# PlanktoscopeHat-v1_0-fab.net
KiCad netlist of a schematic drawn in EAGLE
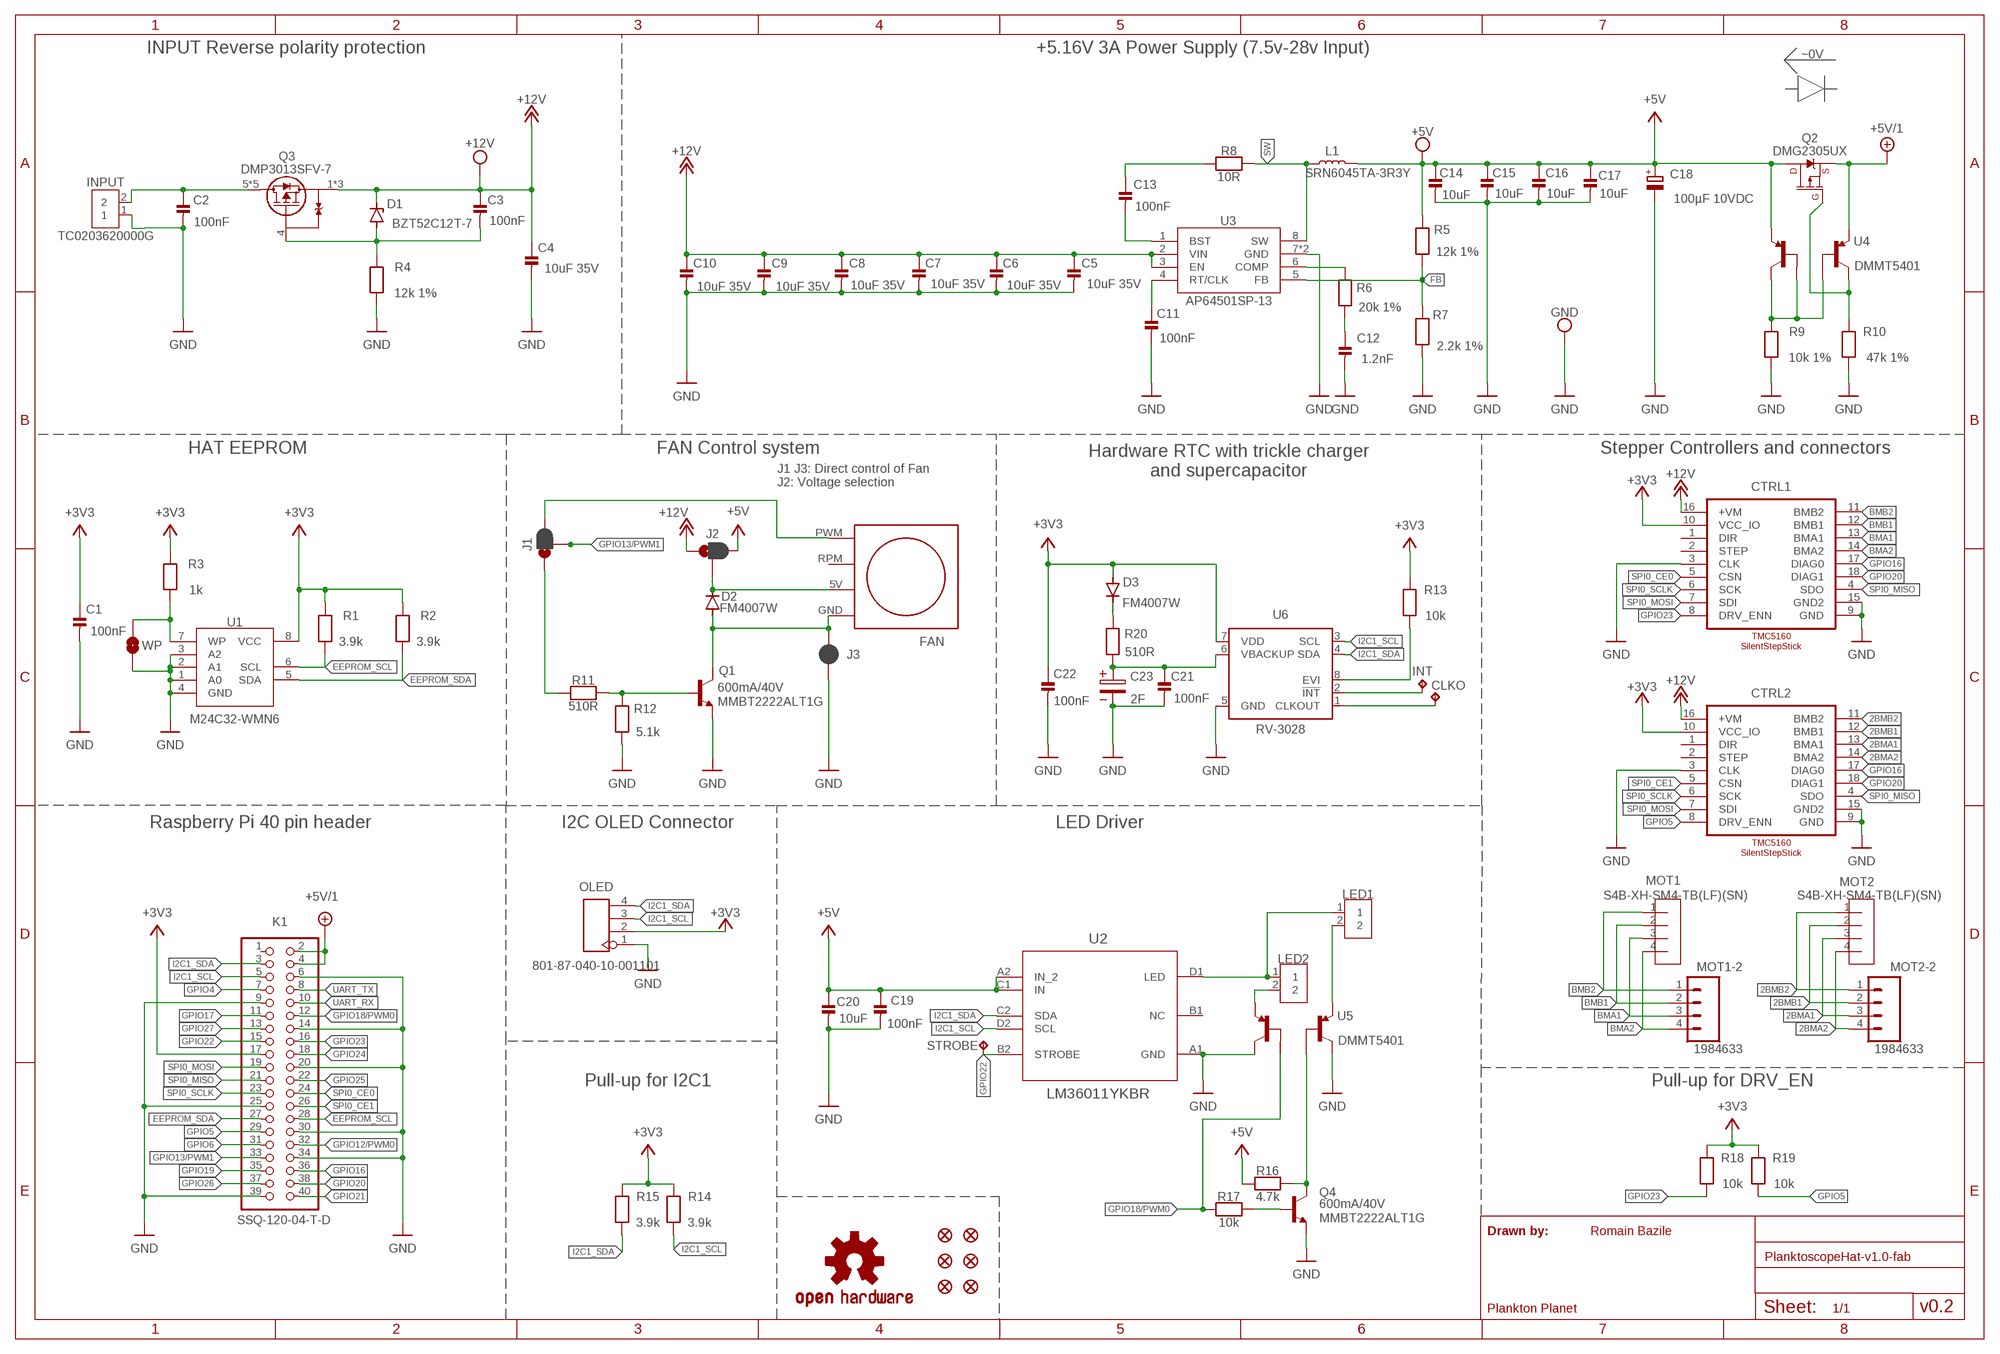
[diagram p0: schematic, sheet 1]

(export (version "E")
  (design (tool "Eeschema 10.0.6"))
  (components
    (comp (ref "+5V")
      (value "TESTPOINTPAD2MM")
      (footprint "eagle-import:TESTPOINT_PAD_2MM")
      (libsource (lib "eagle-import") (part "TESTPOINTPAD2MM"))
    )
    (comp (ref "+12V")
      (value "TESTPOINTPAD2MM")
      (footprint "eagle-import:TESTPOINT_PAD_2MM")
      (libsource (lib "eagle-import") (part "TESTPOINTPAD2MM"))
    )
    (comp (ref "C1")
      (value "100nF")
      (footprint "eagle-import:_0805MP")
      (libsource (lib "eagle-import") (part "CAP_CERAMIC_0805MP"))
    )
    (comp (ref "C2")
      (value "100nF")
      (footprint "eagle-import:_0805MP")
      (libsource (lib "eagle-import") (part "CAP_CERAMIC_0805MP"))
    )
    (comp (ref "C3")
      (value "100nF")
      (footprint "eagle-import:_0805MP")
      (libsource (lib "eagle-import") (part "CAP_CERAMIC_0805MP"))
    )
    (comp (ref "C4")
      (value "10uF 35V")
      (footprint "eagle-import:_0805MP")
      (libsource (lib "eagle-import") (part "CAP_CERAMIC_0805MP"))
    )
    (comp (ref "C5")
      (value "10uF 35V")
      (footprint "eagle-import:_0805MP")
      (libsource (lib "eagle-import") (part "CAP_CERAMIC_0805MP"))
    )
    (comp (ref "C6")
      (value "10uF 35V")
      (footprint "eagle-import:_0805MP")
      (libsource (lib "eagle-import") (part "CAP_CERAMIC_0805MP"))
    )
    (comp (ref "C7")
      (value "10uF 35V")
      (footprint "eagle-import:_0805MP")
      (libsource (lib "eagle-import") (part "CAP_CERAMIC_0805MP"))
    )
    (comp (ref "C8")
      (value "10uF 35V")
      (footprint "eagle-import:_0805MP")
      (libsource (lib "eagle-import") (part "CAP_CERAMIC_0805MP"))
    )
    (comp (ref "C9")
      (value "10uF 35V")
      (footprint "eagle-import:_0805MP")
      (libsource (lib "eagle-import") (part "CAP_CERAMIC_0805MP"))
    )
    (comp (ref "C10")
      (value "10uF 35V")
      (footprint "eagle-import:_0805MP")
      (libsource (lib "eagle-import") (part "CAP_CERAMIC_0805MP"))
    )
    (comp (ref "C11")
      (value "100nF")
      (footprint "eagle-import:_0805MP")
      (libsource (lib "eagle-import") (part "CAP_CERAMIC_0805MP"))
    )
    (comp (ref "C12")
      (value "1.2nF")
      (footprint "eagle-import:_0805MP")
      (libsource (lib "eagle-import") (part "CAP_CERAMIC_0805MP"))
    )
    (comp (ref "C13")
      (value "100nF")
      (footprint "eagle-import:_0805MP")
      (libsource (lib "eagle-import") (part "CAP_CERAMIC_0805MP"))
    )
    (comp (ref "C14")
      (value "10uF")
      (footprint "eagle-import:_0805MP")
      (libsource (lib "eagle-import") (part "CAP_CERAMIC_0805MP"))
    )
    (comp (ref "C15")
      (value "10uF")
      (footprint "eagle-import:_0805MP")
      (libsource (lib "eagle-import") (part "CAP_CERAMIC_0805MP"))
    )
    (comp (ref "C16")
      (value "10uF")
      (footprint "eagle-import:_0805MP")
      (libsource (lib "eagle-import") (part "CAP_CERAMIC_0805MP"))
    )
    (comp (ref "C17")
      (value "10uF")
      (footprint "eagle-import:_0805MP")
      (libsource (lib "eagle-import") (part "CAP_CERAMIC_0805MP"))
    )
    (comp (ref "C18")
      (value "100µF 10VDC")
      (footprint "eagle-import:CAPMP6032X280N")
      (fields (field (name "MPN") "TPSC107K010T0200"))
      (libsource (lib "eagle-import") (part "C-POLTANTALUM-2412(6032-METRIC)_"))
    )
    (comp (ref "C19")
      (value "100nF")
      (footprint "eagle-import:_0805MP")
      (libsource (lib "eagle-import") (part "CAP_CERAMIC_0805MP"))
    )
    (comp (ref "C20")
      (value "10uF")
      (footprint "eagle-import:_0805MP")
      (libsource (lib "eagle-import") (part "CAP_CERAMIC_0805MP"))
    )
    (comp (ref "C21")
      (value "100nF")
      (footprint "eagle-import:_0805MP")
      (libsource (lib "eagle-import") (part "CAP_CERAMIC_0805MP"))
    )
    (comp (ref "C22")
      (value "100nF")
      (footprint "eagle-import:_0805MP")
      (libsource (lib "eagle-import") (part "CAP_CERAMIC_0805MP"))
    )
    (comp (ref "C23")
      (value "2F")
      (footprint "eagle-import:8X3.5X0.9(DXAXB)")
      (fields (field (name "MPN") "SCCR12E105SRB"))
      (libsource (lib "eagle-import") (part "WCAP-PTHT_870135174001_8X8"))
    )
    (comp (ref "CLKO")
      (value "TPB1,27")
      (footprint "eagle-import:B1,27")
      (libsource (lib "eagle-import") (part "TPB1,27"))
    )
    (comp (ref "CTRL1")
      (value "TMC5160_SILENTSTEPSTICK")
      (footprint "eagle-import:TMC5160_STEPSTICK")
      (libsource (lib "eagle-import") (part "TMC5160_SILENTSTEPSTICK"))
    )
    (comp (ref "CTRL2")
      (value "TMC5160_SILENTSTEPSTICK")
      (footprint "eagle-import:TMC5160_STEPSTICK")
      (libsource (lib "eagle-import") (part "TMC5160_SILENTSTEPSTICK"))
    )
    (comp (ref "D1")
      (value "BZT52C12T-7")
      (footprint "eagle-import:SODFL1608X70")
      (libsource (lib "eagle-import") (part "ZENERSODFL(1608-METRIC)_"))
    )
    (comp (ref "D2")
      (value "FM4007W")
      (footprint "eagle-import:DO-214AC")
      (libsource (lib "eagle-import") (part "DIODE-DO-214AC"))
    )
    (comp (ref "D3")
      (value "FM4007W")
      (footprint "eagle-import:DO-214AC")
      (libsource (lib "eagle-import") (part "DIODE-DO-214AC"))
    )
    (comp (ref "FAN")
      (value "40MM_FAN")
      (footprint "eagle-import:40MM_FAN")
      (libsource (lib "eagle-import") (part "40MM_FAN"))
    )
    (comp (ref "FD1")
      (value "FIDUCIAL1X2")
      (footprint "eagle-import:FIDUCIAL-1X2")
      (libsource (lib "eagle-import") (part "FIDUCIAL1X2"))
    )
    (comp (ref "FD2")
      (value "FIDUCIAL1X2")
      (footprint "eagle-import:FIDUCIAL-1X2")
      (libsource (lib "eagle-import") (part "FIDUCIAL1X2"))
    )
    (comp (ref "FD3")
      (value "FIDUCIAL1X2")
      (footprint "eagle-import:FIDUCIAL-1X2")
      (libsource (lib "eagle-import") (part "FIDUCIAL1X2"))
    )
    (comp (ref "FD4")
      (value "FIDUCIAL1X2")
      (footprint "eagle-import:FIDUCIAL-1X2")
      (libsource (lib "eagle-import") (part "FIDUCIAL1X2"))
    )
    (comp (ref "FD5")
      (value "FIDUCIAL1X2")
      (footprint "eagle-import:FIDUCIAL-1X2")
      (libsource (lib "eagle-import") (part "FIDUCIAL1X2"))
    )
    (comp (ref "FD6")
      (value "FIDUCIAL1X2")
      (footprint "eagle-import:FIDUCIAL-1X2")
      (libsource (lib "eagle-import") (part "FIDUCIAL1X2"))
    )
    (comp (ref "GND")
      (value "TESTPOINTPAD2MM")
      (footprint "eagle-import:TESTPOINT_PAD_2MM")
      (libsource (lib "eagle-import") (part "TESTPOINTPAD2MM"))
    )
    (comp (ref "INPUT")
      (value "TC0203620000G")
      (footprint "eagle-import:TERMBLK_508-2N")
      (fields
        (field (name "MANUFACTURER") "TE Connectivity")
        (field (name "MPN") "282837-2")
        (field (name "MPN_1") "TC0203620000G")
      )
      (libsource (lib "eagle-import") (part "2828XX-2282837-2"))
    )
    (comp (ref "INT")
      (value "TPB1,27")
      (footprint "eagle-import:B1,27")
      (libsource (lib "eagle-import") (part "TPB1,27"))
    )
    (comp (ref "J1")
      (value "JUMPER-SMT_3_1-NC_PASTE_SILK")
      (footprint "eagle-import:SMT-JUMPER_3_1-NC_PASTE_SILK")
      (libsource (lib "eagle-import") (part "JUMPER-SMT_3_1-NC_PASTE_SILK"))
    )
    (comp (ref "J2")
      (value "JUMPER-SMT_3_1-NC_PASTE_SILK")
      (footprint "eagle-import:SMT-JUMPER_3_1-NC_PASTE_SILK")
      (libsource (lib "eagle-import") (part "JUMPER-SMT_3_1-NC_PASTE_SILK"))
    )
    (comp (ref "J3")
      (value "JUMPER-SMT_2_NC_PASTE_SILK")
      (footprint "eagle-import:SMT-JUMPER_2_NC_PASTE_SILK")
      (libsource (lib "eagle-import") (part "JUMPER-SMT_2_NC_PASTE_SILK"))
    )
    (comp (ref "K1")
      (value "SSQ-120-04-T-D")
      (footprint "eagle-import:2X20")
      (libsource (lib "eagle-import") (part "PINHD-2X20"))
    )
    (comp (ref "L1")
      (value "SRN6045TA-3R3Y")
      (footprint "eagle-import:SRN6045")
      (libsource (lib "eagle-import") (part "INDUCTOR-SRN6045-33UH"))
    )
    (comp (ref "LED1")
      (value "2828XX-2282834-2")
      (footprint "eagle-import:TERMBLK_254-2N")
      (libsource (lib "eagle-import") (part "2828XX-2282834-2"))
    )
    (comp (ref "LED2")
      (value "2828XX-2282834-2")
      (footprint "eagle-import:TERMBLK_254-2N")
      (libsource (lib "eagle-import") (part "2828XX-2282834-2"))
    )
    (comp (ref "LOGO1")
      (value "OSHW-LOGOL")
      (footprint "eagle-import:OSHW-LOGO-L")
      (libsource (lib "eagle-import") (part "OSHW-LOGOL"))
    )
    (comp (ref "MOT1")
      (value "S4B-XH-SM4-TB(LF)(SN)")
      (footprint "eagle-import:CONN_S4B-XH-SM4-TB_JST")
      (fields
        (field (name "MPN") "S4B-XH-SM4-TB(LF)(SN)")
        (field (name "COPYRIGHT") "Copyright (C) 2018 Accelerated Designs. All rights reserved")
      )
      (libsource (lib "eagle-import") (part "S4B-XH-SM4-TB(LF)(SN)"))
    )
    (comp (ref "MOT1-2")
      (value "1984633")
      (footprint "eagle-import:SCREWTERMINAL-3.5MM-4")
      (libsource (lib "eagle-import") (part "CONN_04SCREW"))
    )
    (comp (ref "MOT2")
      (value "S4B-XH-SM4-TB(LF)(SN)")
      (footprint "eagle-import:CONN_S4B-XH-SM4-TB_JST")
      (fields
        (field (name "MPN") "S4B-XH-SM4-TB(LF)(SN)")
        (field (name "COPYRIGHT") "Copyright (C) 2018 Accelerated Designs. All rights reserved")
      )
      (libsource (lib "eagle-import") (part "S4B-XH-SM4-TB(LF)(SN)"))
    )
    (comp (ref "MOT2-2")
      (value "1984633")
      (footprint "eagle-import:SCREWTERMINAL-3.5MM-4")
      (libsource (lib "eagle-import") (part "CONN_04SCREW"))
    )
    (comp (ref "OLED")
      (value "801-87-040-10-001101")
      (footprint "eagle-import:H4-2.54")
      (fields (field (name "MPN") "P125-1104A0BS116A1"))
      (libsource (lib "eagle-import") (part "DIP-BLACK-MALE-HEADER-VERT(4P-2.54)"))
    )
    (comp (ref "Q1")
      (value "600mA/40V")
      (footprint "eagle-import:SOT23-3")
      (fields (field (name "MPN") "MMBT2222ALT1G"))
      (libsource (lib "eagle-import") (part "TRANS_NPN-MMBT2222AL"))
    )
    (comp (ref "Q2")
      (value "DMG2305UX")
      (footprint "eagle-import:SOT23-3")
      (libsource (lib "eagle-import") (part "MOSFET_PCH-DMG2305UX-7"))
    )
    (comp (ref "Q3")
      (value "DMP3013SFV-7")
      (footprint "eagle-import:POWERDI3333-8_UX_DIO")
      (fields (field (name "COPYRIGHT") "Copyright (C) 2018 Accelerated Designs. All rights reserved"))
      (libsource (lib "eagle-import") (part "DMP3013SFV-7"))
    )
    (comp (ref "Q4")
      (value "600mA/40V")
      (footprint "eagle-import:SOT23-3")
      (fields (field (name "MPN") "MMBT2222ALT1G"))
      (libsource (lib "eagle-import") (part "TRANS_NPN-MMBT2222AL"))
    )
    (comp (ref "R1")
      (value "3.9k")
      (footprint "eagle-import:_0805MP")
      (libsource (lib "eagle-import") (part "RESISTOR_0805MP"))
    )
    (comp (ref "R2")
      (value "3.9k")
      (footprint "eagle-import:_0805MP")
      (libsource (lib "eagle-import") (part "RESISTOR_0805MP"))
    )
    (comp (ref "R3")
      (value "1k")
      (footprint "eagle-import:_0805MP")
      (libsource (lib "eagle-import") (part "RESISTOR_0805MP"))
    )
    (comp (ref "R4")
      (value "12k 1%")
      (footprint "eagle-import:_0805MP")
      (libsource (lib "eagle-import") (part "RESISTOR_0805MP"))
    )
    (comp (ref "R5")
      (value "12k 1%")
      (footprint "eagle-import:_0805MP")
      (libsource (lib "eagle-import") (part "RESISTOR_0805MP"))
    )
    (comp (ref "R6")
      (value "20k 1%")
      (footprint "eagle-import:_0805MP")
      (libsource (lib "eagle-import") (part "RESISTOR_0805MP"))
    )
    (comp (ref "R7")
      (value "2.2k 1%")
      (footprint "eagle-import:_0805MP")
      (libsource (lib "eagle-import") (part "RESISTOR_0805MP"))
    )
    (comp (ref "R8")
      (value "10R")
      (footprint "eagle-import:_0805MP")
      (libsource (lib "eagle-import") (part "RESISTOR_0805MP"))
    )
    (comp (ref "R9")
      (value "10k 1%")
      (footprint "eagle-import:_0805MP")
      (libsource (lib "eagle-import") (part "RESISTOR_0805MP"))
    )
    (comp (ref "R10")
      (value "47k 1%")
      (footprint "eagle-import:_0805MP")
      (libsource (lib "eagle-import") (part "RESISTOR_0805MP"))
    )
    (comp (ref "R11")
      (value "510R")
      (footprint "eagle-import:_0805MP")
      (libsource (lib "eagle-import") (part "RESISTOR_0805MP"))
    )
    (comp (ref "R12")
      (value "5.1k")
      (footprint "eagle-import:_0805MP")
      (libsource (lib "eagle-import") (part "RESISTOR_0805MP"))
    )
    (comp (ref "R13")
      (value "10k")
      (footprint "eagle-import:_0805MP")
      (libsource (lib "eagle-import") (part "RESISTOR_0805MP"))
    )
    (comp (ref "R14")
      (value "3.9k")
      (footprint "eagle-import:_0805MP")
      (libsource (lib "eagle-import") (part "RESISTOR_0805MP"))
    )
    (comp (ref "R15")
      (value "3.9k")
      (footprint "eagle-import:_0805MP")
      (libsource (lib "eagle-import") (part "RESISTOR_0805MP"))
    )
    (comp (ref "R16")
      (value "4.7k")
      (footprint "eagle-import:_0805MP")
      (libsource (lib "eagle-import") (part "RESISTOR_0805MP"))
    )
    (comp (ref "R17")
      (value "10k")
      (footprint "eagle-import:_0805MP")
      (libsource (lib "eagle-import") (part "RESISTOR_0805MP"))
    )
    (comp (ref "R18")
      (value "10k")
      (footprint "eagle-import:_0805MP")
      (libsource (lib "eagle-import") (part "RESISTOR_0805MP"))
    )
    (comp (ref "R19")
      (value "10k")
      (footprint "eagle-import:_0805MP")
      (libsource (lib "eagle-import") (part "RESISTOR_0805MP"))
    )
    (comp (ref "R20")
      (value "510R")
      (footprint "eagle-import:_0805MP")
      (libsource (lib "eagle-import") (part "RESISTOR_0805MP"))
    )
    (comp (ref "STROBE")
      (value "TPTP15R")
      (footprint "eagle-import:TP15R")
      (libsource (lib "eagle-import") (part "TPTP15R"))
    )
    (comp (ref "U1")
      (value "M24C32-WMN6")
      (footprint "eagle-import:SO-8_STM")
      (libsource (lib "eagle-import") (part "M24C32-WMN6"))
    )
    (comp (ref "U2")
      (value "LM36011YKBR")
      (footprint "eagle-import:YKB0008AGAG")
      (fields (field (name "MANUFACTURER") "Texas Instruments"))
      (libsource (lib "eagle-import") (part "LM36011YKBR"))
    )
    (comp (ref "U3")
      (value "AP64501SP-13")
      (footprint "eagle-import:SO-8EP_DIO")
      (fields
        (field (name "MANUFACTURER_PART_NUMBER") "AP64500SP-13")
        (field (name "COPYRIGHT") "Copyright (C) 2018 Accelerated Designs. All rights reserved")
      )
      (libsource (lib "eagle-import") (part "AP64500SP-13"))
    )
    (comp (ref "U4")
      (value "DMMT5401")
      (footprint "eagle-import:SOT26")
      (libsource (lib "eagle-import") (part "DDMT5401"))
    )
    (comp (ref "U5")
      (value "DMMT5401")
      (footprint "eagle-import:SOT26")
      (libsource (lib "eagle-import") (part "DDMT5401"))
    )
    (comp (ref "U6")
      (value "RV-3028")
      (footprint "eagle-import:RV-3028")
      (libsource (lib "eagle-import") (part "RV-3028"))
    )
    (comp (ref "WP")
      (value "JUMPER-SMT_2_NO_SILK")
      (footprint "eagle-import:SMT-JUMPER_2_NO_SILK")
      (libsource (lib "eagle-import") (part "JUMPER-SMT_2_NO_SILK"))
    )
  )
  (nets
    (net (code "1") (name "+3V3") (class "Default")
      (node (ref "C1") (pin "1") (pinfunction "1_1") (pintype "passive"))
      (node (ref "C22") (pin "1") (pinfunction "1_1") (pintype "passive"))
      (node (ref "CTRL1") (pin "10") (pinfunction "VCC_IO_10") (pintype "passive"))
      (node (ref "CTRL2") (pin "10") (pinfunction "VCC_IO_10") (pintype "passive"))
      (node (ref "D3") (pin "A") (pinfunction "A_A") (pintype "passive"))
      (node (ref "K1") (pin "17") (pinfunction "17_17") (pintype "passive"))
      (node (ref "OLED") (pin "2") (pinfunction "P$2_2") (pintype "bidirectional"))
      (node (ref "R1") (pin "2") (pinfunction "2_2") (pintype "passive"))
      (node (ref "R13") (pin "2") (pinfunction "2_2") (pintype "passive"))
      (node (ref "R14") (pin "2") (pinfunction "2_2") (pintype "passive"))
      (node (ref "R15") (pin "2") (pinfunction "2_2") (pintype "passive"))
      (node (ref "R18") (pin "2") (pinfunction "2_2") (pintype "passive"))
      (node (ref "R19") (pin "2") (pinfunction "2_2") (pintype "passive"))
      (node (ref "R2") (pin "2") (pinfunction "2_2") (pintype "passive"))
      (node (ref "R3") (pin "2") (pinfunction "2_2") (pintype "passive"))
      (node (ref "U1") (pin "8") (pinfunction "VCC_8") (pintype "power_in"))
      (node (ref "U6") (pin "7") (pinfunction "VDD_7") (pintype "bidirectional"))
    )
    (net (code "2") (name "+5V") (class "Default")
      (node (ref "+5V") (pin "P$1") (pinfunction "P$1_P$1") (pintype "bidirectional"))
      (node (ref "C14") (pin "1") (pinfunction "1_1") (pintype "passive"))
      (node (ref "C15") (pin "1") (pinfunction "1_1") (pintype "passive"))
      (node (ref "C16") (pin "1") (pinfunction "1_1") (pintype "passive"))
      (node (ref "C17") (pin "1") (pinfunction "1_1") (pintype "passive"))
      (node (ref "C18") (pin "1") (pinfunction "+_1") (pintype "passive"))
      (node (ref "C19") (pin "1") (pinfunction "1_1") (pintype "passive"))
      (node (ref "C20") (pin "1") (pinfunction "1_1") (pintype "passive"))
      (node (ref "J2") (pin "3") (pinfunction "3_3") (pintype "passive"))
      (node (ref "L1") (pin "2") (pinfunction "2_2") (pintype "passive"))
      (node (ref "Q2") (pin "3") (pinfunction "D_3") (pintype "bidirectional"))
      (node (ref "R16") (pin "2") (pinfunction "2_2") (pintype "passive"))
      (node (ref "R5") (pin "2") (pinfunction "2_2") (pintype "passive"))
      (node (ref "U2") (pin "A2") (pinfunction "IN_2_A2") (pintype "power_in"))
      (node (ref "U2") (pin "C1") (pinfunction "IN_C1") (pintype "power_in"))
      (node (ref "U4") (pin "D1") (pinfunction "6_D1") (pintype "passive"))
    )
    (net (code "3") (name "+5V{slash}1") (class "Default")
      (node (ref "K1") (pin "2") (pinfunction "2_2") (pintype "passive"))
      (node (ref "K1") (pin "4") (pinfunction "4_4") (pintype "passive"))
      (node (ref "Q2") (pin "2") (pinfunction "S_2") (pintype "bidirectional"))
      (node (ref "U4") (pin "S1") (pinfunction "5_S1") (pintype "passive"))
    )
    (net (code "4") (name "+12V") (class "Default")
      (node (ref "+12V") (pin "P$1") (pinfunction "P$1_P$1") (pintype "bidirectional"))
      (node (ref "C10") (pin "1") (pinfunction "1_1") (pintype "passive"))
      (node (ref "C3") (pin "1") (pinfunction "1_1") (pintype "passive"))
      (node (ref "C4") (pin "1") (pinfunction "1_1") (pintype "passive"))
      (node (ref "C5") (pin "1") (pinfunction "1_1") (pintype "passive"))
      (node (ref "C6") (pin "1") (pinfunction "1_1") (pintype "passive"))
      (node (ref "C7") (pin "1") (pinfunction "1_1") (pintype "passive"))
      (node (ref "C8") (pin "1") (pinfunction "1_1") (pintype "passive"))
      (node (ref "C9") (pin "1") (pinfunction "1_1") (pintype "passive"))
      (node (ref "CTRL1") (pin "16") (pinfunction "+VM_16") (pintype "passive"))
      (node (ref "CTRL2") (pin "16") (pinfunction "+VM_16") (pintype "passive"))
      (node (ref "D1") (pin "1") (pinfunction "C_1") (pintype "passive"))
      (node (ref "J2") (pin "1") (pinfunction "1_1") (pintype "passive"))
      (node (ref "Q3") (pin "1") (pinfunction "S_1") (pintype "passive"))
      (node (ref "Q3") (pin "2") (pinfunction "S_2") (pintype "passive"))
      (node (ref "Q3") (pin "3") (pinfunction "S_3") (pintype "passive"))
      (node (ref "U3") (pin "2") (pinfunction "VIN_2") (pintype "power_in"))
      (node (ref "U3") (pin "3") (pinfunction "EN_3") (pintype "input"))
    )
    (net (code "5") (name "2BMA1") (class "Default")
      (node (ref "CTRL2") (pin "13") (pinfunction "BMA1_13") (pintype "passive"))
      (node (ref "MOT2") (pin "3") (pinfunction "3_3") (pintype "passive"))
      (node (ref "MOT2-2") (pin "3") (pinfunction "3_3") (pintype "passive"))
    )
    (net (code "6") (name "2BMA2") (class "Default")
      (node (ref "CTRL2") (pin "14") (pinfunction "BMA2_14") (pintype "passive"))
      (node (ref "MOT2") (pin "4") (pinfunction "4_4") (pintype "passive"))
      (node (ref "MOT2-2") (pin "4") (pinfunction "4_4") (pintype "passive"))
    )
    (net (code "7") (name "2BMB1") (class "Default")
      (node (ref "CTRL2") (pin "12") (pinfunction "BMB1_12") (pintype "passive"))
      (node (ref "MOT2") (pin "2") (pinfunction "2_2") (pintype "passive"))
      (node (ref "MOT2-2") (pin "2") (pinfunction "2_2") (pintype "passive"))
    )
    (net (code "8") (name "2BMB2") (class "Default")
      (node (ref "CTRL2") (pin "11") (pinfunction "BMB2_11") (pintype "passive"))
      (node (ref "MOT2") (pin "1") (pinfunction "1_1") (pintype "passive"))
      (node (ref "MOT2-2") (pin "1") (pinfunction "1_1") (pintype "passive"))
    )
    (net (code "9") (name "BMA1") (class "Default")
      (node (ref "CTRL1") (pin "13") (pinfunction "BMA1_13") (pintype "passive"))
      (node (ref "MOT1") (pin "3") (pinfunction "3_3") (pintype "passive"))
      (node (ref "MOT1-2") (pin "3") (pinfunction "3_3") (pintype "passive"))
    )
    (net (code "10") (name "BMA2") (class "Default")
      (node (ref "CTRL1") (pin "14") (pinfunction "BMA2_14") (pintype "passive"))
      (node (ref "MOT1") (pin "4") (pinfunction "4_4") (pintype "passive"))
      (node (ref "MOT1-2") (pin "4") (pinfunction "4_4") (pintype "passive"))
    )
    (net (code "11") (name "BMB1") (class "Default")
      (node (ref "CTRL1") (pin "12") (pinfunction "BMB1_12") (pintype "passive"))
      (node (ref "MOT1") (pin "2") (pinfunction "2_2") (pintype "passive"))
      (node (ref "MOT1-2") (pin "2") (pinfunction "2_2") (pintype "passive"))
    )
    (net (code "12") (name "BMB2") (class "Default")
      (node (ref "CTRL1") (pin "11") (pinfunction "BMB2_11") (pintype "passive"))
      (node (ref "MOT1") (pin "1") (pinfunction "1_1") (pintype "passive"))
      (node (ref "MOT1-2") (pin "1") (pinfunction "1_1") (pintype "passive"))
    )
    (net (code "13") (name "EEPROM_SCL") (class "Default")
      (node (ref "K1") (pin "28") (pinfunction "28_28") (pintype "passive"))
      (node (ref "R1") (pin "1") (pinfunction "1_1") (pintype "passive"))
      (node (ref "U1") (pin "6") (pinfunction "SCL_6") (pintype "input"))
    )
    (net (code "14") (name "EEPROM_SDA") (class "Default")
      (node (ref "K1") (pin "27") (pinfunction "27_27") (pintype "passive"))
      (node (ref "R2") (pin "1") (pinfunction "1_1") (pintype "passive"))
      (node (ref "U1") (pin "5") (pinfunction "SDA_5") (pintype "bidirectional"))
    )
    (net (code "15") (name "FB") (class "Default")
      (node (ref "R5") (pin "1") (pinfunction "1_1") (pintype "passive"))
      (node (ref "R7") (pin "2") (pinfunction "2_2") (pintype "passive"))
      (node (ref "U3") (pin "5") (pinfunction "FB_5") (pintype "passive"))
    )
    (net (code "16") (name "GND") (class "Default")
      (node (ref "C1") (pin "2") (pinfunction "2_2") (pintype "passive"))
      (node (ref "C10") (pin "2") (pinfunction "2_2") (pintype "passive"))
      (node (ref "C11") (pin "2") (pinfunction "2_2") (pintype "passive"))
      (node (ref "C12") (pin "2") (pinfunction "2_2") (pintype "passive"))
      (node (ref "C14") (pin "2") (pinfunction "2_2") (pintype "passive"))
      (node (ref "C15") (pin "2") (pinfunction "2_2") (pintype "passive"))
      (node (ref "C16") (pin "2") (pinfunction "2_2") (pintype "passive"))
      (node (ref "C17") (pin "2") (pinfunction "2_2") (pintype "passive"))
      (node (ref "C18") (pin "2") (pinfunction "-_2") (pintype "passive"))
      (node (ref "C19") (pin "2") (pinfunction "2_2") (pintype "passive"))
      (node (ref "C2") (pin "2") (pinfunction "2_2") (pintype "passive"))
      (node (ref "C20") (pin "2") (pinfunction "2_2") (pintype "passive"))
      (node (ref "C21") (pin "2") (pinfunction "2_2") (pintype "passive"))
      (node (ref "C22") (pin "2") (pinfunction "2_2") (pintype "passive"))
      (node (ref "C23") (pin "2") (pinfunction "2_2") (pintype "passive"))
      (node (ref "C4") (pin "2") (pinfunction "2_2") (pintype "passive"))
      (node (ref "C5") (pin "2") (pinfunction "2_2") (pintype "passive"))
      (node (ref "C6") (pin "2") (pinfunction "2_2") (pintype "passive"))
      (node (ref "C7") (pin "2") (pinfunction "2_2") (pintype "passive"))
      (node (ref "C8") (pin "2") (pinfunction "2_2") (pintype "passive"))
      (node (ref "C9") (pin "2") (pinfunction "2_2") (pintype "passive"))
      (node (ref "CTRL1") (pin "15") (pinfunction "GND2_15") (pintype "passive"))
      (node (ref "CTRL1") (pin "3") (pinfunction "CLK_3") (pintype "passive"))
      (node (ref "CTRL1") (pin "9") (pinfunction "GND_9") (pintype "passive"))
      (node (ref "CTRL2") (pin "15") (pinfunction "GND2_15") (pintype "passive"))
      (node (ref "CTRL2") (pin "3") (pinfunction "CLK_3") (pintype "passive"))
      (node (ref "CTRL2") (pin "9") (pinfunction "GND_9") (pintype "passive"))
      (node (ref "GND") (pin "P$1") (pinfunction "P$1_P$1") (pintype "bidirectional"))
      (node (ref "INPUT") (pin "1") (pinfunction "1_1") (pintype "bidirectional"))
      (node (ref "J3") (pin "1") (pinfunction "1_1") (pintype "passive"))
      (node (ref "K1") (pin "14") (pinfunction "14_14") (pintype "passive"))
      (node (ref "K1") (pin "20") (pinfunction "20_20") (pintype "passive"))
      (node (ref "K1") (pin "25") (pinfunction "25_25") (pintype "passive"))
      (node (ref "K1") (pin "30") (pinfunction "30_30") (pintype "passive"))
      (node (ref "K1") (pin "34") (pinfunction "34_34") (pintype "passive"))
      (node (ref "K1") (pin "39") (pinfunction "39_39") (pintype "passive"))
      (node (ref "K1") (pin "6") (pinfunction "6_6") (pintype "passive"))
      (node (ref "K1") (pin "9") (pinfunction "9_9") (pintype "passive"))
      (node (ref "OLED") (pin "1") (pinfunction "P$1_1") (pintype "bidirectional"))
      (node (ref "Q1") (pin "2") (pinfunction "E_2") (pintype "passive"))
      (node (ref "Q4") (pin "2") (pinfunction "E_2") (pintype "passive"))
      (node (ref "R10") (pin "1") (pinfunction "1_1") (pintype "passive"))
      (node (ref "R12") (pin "1") (pinfunction "1_1") (pintype "passive"))
      (node (ref "R4") (pin "1") (pinfunction "1_1") (pintype "passive"))
      (node (ref "R7") (pin "1") (pinfunction "1_1") (pintype "passive"))
      (node (ref "R9") (pin "1") (pinfunction "1_1") (pintype "passive"))
      (node (ref "U1") (pin "1") (pinfunction "A0_1") (pintype "input"))
      (node (ref "U1") (pin "2") (pinfunction "A1_2") (pintype "input"))
      (node (ref "U1") (pin "3") (pinfunction "A2_3") (pintype "input"))
      (node (ref "U1") (pin "4") (pinfunction "GND_4") (pintype "power_in"))
      (node (ref "U2") (pin "A1") (pinfunction "GND_A1") (pintype "power_in"))
      (node (ref "U3") (pin "7") (pinfunction "GND_7") (pintype "passive"))
      (node (ref "U3") (pin "EPAD") (pinfunction "GND_EPAD") (pintype "passive"))
      (node (ref "U5") (pin "D2") (pinfunction "4_D2") (pintype "passive"))
      (node (ref "U5") (pin "G1") (pinfunction "1_G1") (pintype "passive"))
      (node (ref "U6") (pin "5") (pinfunction "GND_5") (pintype "bidirectional"))
      (node (ref "WP") (pin "1") (pinfunction "1_1") (pintype "passive"))
    )
    (net (code "17") (name "GPIO4") (class "Default")
      (node (ref "K1") (pin "7") (pinfunction "7_7") (pintype "passive"))
    )
    (net (code "18") (name "GPIO5") (class "Default")
      (node (ref "CTRL2") (pin "8") (pinfunction "DRV_ENN_8") (pintype "passive"))
      (node (ref "K1") (pin "29") (pinfunction "29_29") (pintype "passive"))
      (node (ref "R19") (pin "1") (pinfunction "1_1") (pintype "passive"))
    )
    (net (code "19") (name "GPIO6") (class "Default")
      (node (ref "K1") (pin "31") (pinfunction "31_31") (pintype "passive"))
    )
    (net (code "20") (name "GPIO12{slash}PWM0") (class "Default")
      (node (ref "K1") (pin "32") (pinfunction "32_32") (pintype "passive"))
    )
    (net (code "21") (name "GPIO13{slash}PWM1") (class "Default")
      (node (ref "J1") (pin "2") (pinfunction "2_2") (pintype "passive"))
      (node (ref "K1") (pin "33") (pinfunction "33_33") (pintype "passive"))
    )
    (net (code "22") (name "GPIO16") (class "Default")
      (node (ref "CTRL1") (pin "17") (pinfunction "DIAG0_17") (pintype "passive"))
      (node (ref "CTRL2") (pin "17") (pinfunction "DIAG0_17") (pintype "passive"))
      (node (ref "K1") (pin "36") (pinfunction "36_36") (pintype "passive"))
    )
    (net (code "23") (name "GPIO17") (class "Default")
      (node (ref "K1") (pin "11") (pinfunction "11_11") (pintype "passive"))
    )
    (net (code "24") (name "GPIO18{slash}PWM0") (class "Default")
      (node (ref "K1") (pin "12") (pinfunction "12_12") (pintype "passive"))
      (node (ref "R17") (pin "1") (pinfunction "1_1") (pintype "passive"))
      (node (ref "U5") (pin "S2") (pinfunction "2_S2") (pintype "passive"))
    )
    (net (code "25") (name "GPIO19") (class "Default")
      (node (ref "K1") (pin "35") (pinfunction "35_35") (pintype "passive"))
    )
    (net (code "26") (name "GPIO20") (class "Default")
      (node (ref "CTRL1") (pin "18") (pinfunction "DIAG1_18") (pintype "passive"))
      (node (ref "CTRL2") (pin "18") (pinfunction "DIAG1_18") (pintype "passive"))
      (node (ref "K1") (pin "38") (pinfunction "38_38") (pintype "passive"))
    )
    (net (code "27") (name "GPIO21") (class "Default")
      (node (ref "K1") (pin "40") (pinfunction "40_40") (pintype "passive"))
    )
    (net (code "28") (name "GPIO22") (class "Default")
      (node (ref "K1") (pin "15") (pinfunction "15_15") (pintype "passive"))
      (node (ref "STROBE") (pin "TP") (pinfunction "TP_TP") (pintype "input"))
      (node (ref "U2") (pin "B2") (pinfunction "STROBE_B2") (pintype "input"))
    )
    (net (code "29") (name "GPIO23") (class "Default")
      (node (ref "CTRL1") (pin "8") (pinfunction "DRV_ENN_8") (pintype "passive"))
      (node (ref "K1") (pin "16") (pinfunction "16_16") (pintype "passive"))
      (node (ref "R18") (pin "1") (pinfunction "1_1") (pintype "passive"))
    )
    (net (code "30") (name "GPIO24") (class "Default")
      (node (ref "K1") (pin "18") (pinfunction "18_18") (pintype "passive"))
    )
    (net (code "31") (name "GPIO25") (class "Default")
      (node (ref "K1") (pin "22") (pinfunction "22_22") (pintype "passive"))
    )
    (net (code "32") (name "GPIO26") (class "Default")
      (node (ref "K1") (pin "37") (pinfunction "37_37") (pintype "passive"))
    )
    (net (code "33") (name "GPIO27") (class "Default")
      (node (ref "K1") (pin "13") (pinfunction "13_13") (pintype "passive"))
    )
    (net (code "34") (name "I2C1_SCL") (class "Default")
      (node (ref "K1") (pin "5") (pinfunction "5_5") (pintype "passive"))
      (node (ref "OLED") (pin "3") (pinfunction "P$3_3") (pintype "bidirectional"))
      (node (ref "R14") (pin "1") (pinfunction "1_1") (pintype "passive"))
      (node (ref "U2") (pin "D2") (pinfunction "SCL_D2") (pintype "input"))
      (node (ref "U6") (pin "3") (pinfunction "SCL_3") (pintype "bidirectional"))
    )
    (net (code "35") (name "I2C1_SDA") (class "Default")
      (node (ref "K1") (pin "3") (pinfunction "3_3") (pintype "passive"))
      (node (ref "OLED") (pin "4") (pinfunction "P$4_4") (pintype "bidirectional"))
      (node (ref "R15") (pin "1") (pinfunction "1_1") (pintype "passive"))
      (node (ref "U2") (pin "C2") (pinfunction "SDA_C2") (pintype "bidirectional"))
      (node (ref "U6") (pin "4") (pinfunction "SDA_4") (pintype "bidirectional"))
    )
    (net (code "36") (name "Net-(C2-Pad1)") (class "Default")
      (node (ref "C2") (pin "1") (pinfunction "1_1") (pintype "passive"))
      (node (ref "INPUT") (pin "2") (pinfunction "2_2") (pintype "bidirectional"))
      (node (ref "Q3") (pin "5") (pinfunction "D_5") (pintype "passive"))
      (node (ref "Q3") (pin "6") (pinfunction "D_6") (pintype "passive"))
      (node (ref "Q3") (pin "7") (pinfunction "D_7") (pintype "passive"))
      (node (ref "Q3") (pin "8") (pinfunction "D_8") (pintype "passive"))
      (node (ref "Q3") (pin "9") (pinfunction "D_9") (pintype "passive"))
    )
    (net (code "37") (name "Net-(C12-Pad1)") (class "Default")
      (node (ref "C12") (pin "1") (pinfunction "1_1") (pintype "passive"))
      (node (ref "R6") (pin "1") (pinfunction "1_1") (pintype "passive"))
    )
    (net (code "38") (name "Net-(C13-Pad1)") (class "Default")
      (node (ref "C13") (pin "1") (pinfunction "1_1") (pintype "passive"))
      (node (ref "R8") (pin "2") (pinfunction "2_2") (pintype "passive"))
    )
    (net (code "39") (name "Net-(D1-A)") (class "Default")
      (node (ref "C3") (pin "2") (pinfunction "2_2") (pintype "passive"))
      (node (ref "D1") (pin "2") (pinfunction "A_2") (pintype "passive"))
      (node (ref "Q3") (pin "4") (pinfunction "G_4") (pintype "passive"))
      (node (ref "R4") (pin "2") (pinfunction "2_2") (pintype "passive"))
    )
    (net (code "40") (name "Net-(D3-PadC)") (class "Default")
      (node (ref "D3") (pin "C") (pinfunction "C_C") (pintype "passive"))
      (node (ref "R20") (pin "2") (pinfunction "2_2") (pintype "passive"))
    )
    (net (code "41") (name "Net-(FAN-+5V)") (class "Default")
      (node (ref "D2") (pin "C") (pinfunction "C_C") (pintype "passive"))
      (node (ref "FAN") (pin "5V") (pinfunction "+5V_5V") (pintype "passive"))
      (node (ref "J2") (pin "2") (pinfunction "2_2") (pintype "passive"))
    )
    (net (code "42") (name "Net-(FAN-PadPWM)") (class "Default")
      (node (ref "FAN") (pin "PWM") (pinfunction "PWM_PWM") (pintype "passive"))
      (node (ref "J1") (pin "3") (pinfunction "3_3") (pintype "passive"))
    )
    (net (code "43") (name "Net-(J1-Pad1)") (class "Default")
      (node (ref "J1") (pin "1") (pinfunction "1_1") (pintype "passive"))
      (node (ref "R11") (pin "1") (pinfunction "1_1") (pintype "passive"))
    )
    (net (code "44") (name "Net-(Q1-B)") (class "Default")
      (node (ref "Q1") (pin "1") (pinfunction "B_1") (pintype "passive"))
      (node (ref "R11") (pin "2") (pinfunction "2_2") (pintype "passive"))
      (node (ref "R12") (pin "2") (pinfunction "2_2") (pintype "passive"))
    )
    (net (code "45") (name "Net-(Q1-C)") (class "Default")
      (node (ref "D2") (pin "A") (pinfunction "A_A") (pintype "passive"))
      (node (ref "FAN") (pin "GND") (pinfunction "GND_GND") (pintype "passive"))
      (node (ref "J3") (pin "2") (pinfunction "2_2") (pintype "passive"))
      (node (ref "Q1") (pin "3") (pinfunction "C_3") (pintype "passive"))
    )
    (net (code "46") (name "Net-(Q2-G)") (class "Default")
      (node (ref "Q2") (pin "1") (pinfunction "G_1") (pintype "bidirectional"))
      (node (ref "R10") (pin "2") (pinfunction "2_2") (pintype "passive"))
      (node (ref "U4") (pin "D2") (pinfunction "4_D2") (pintype "passive"))
    )
    (net (code "47") (name "Net-(Q4-B)") (class "Default")
      (node (ref "Q4") (pin "1") (pinfunction "B_1") (pintype "passive"))
      (node (ref "R17") (pin "2") (pinfunction "2_2") (pintype "passive"))
    )
    (net (code "48") (name "Net-(Q4-C)") (class "Default")
      (node (ref "Q4") (pin "3") (pinfunction "C_3") (pintype "passive"))
      (node (ref "R16") (pin "1") (pinfunction "1_1") (pintype "passive"))
      (node (ref "U5") (pin "G2") (pinfunction "3_G2") (pintype "passive"))
    )
    (net (code "49") (name "Net-(U1-WP)") (class "Default")
      (node (ref "R3") (pin "1") (pinfunction "1_1") (pintype "passive"))
      (node (ref "U1") (pin "7") (pinfunction "WP_7") (pintype "input"))
      (node (ref "WP") (pin "2") (pinfunction "2_2") (pintype "passive"))
    )
    (net (code "50") (name "Net-(U2-LED)") (class "Default")
      (node (ref "LED1") (pin "1") (pinfunction "1_1") (pintype "bidirectional"))
      (node (ref "LED2") (pin "1") (pinfunction "1_1") (pintype "bidirectional"))
      (node (ref "U2") (pin "D1") (pinfunction "LED_D1") (pintype "power_in"))
    )
    (net (code "51") (name "Net-(U3-BST)") (class "Default")
      (node (ref "C13") (pin "2") (pinfunction "2_2") (pintype "passive"))
      (node (ref "U3") (pin "1") (pinfunction "BST_1") (pintype "power_in"))
    )
    (net (code "52") (name "Net-(U3-COMP)") (class "Default")
      (node (ref "R6") (pin "2") (pinfunction "2_2") (pintype "passive"))
      (node (ref "U3") (pin "6") (pinfunction "COMP_6") (pintype "passive"))
    )
    (net (code "53") (name "Net-(U3-RT{slash}CLK)") (class "Default")
      (node (ref "C11") (pin "1") (pinfunction "1_1") (pintype "passive"))
      (node (ref "U3") (pin "4") (pinfunction "RT/CLK_4") (pintype "passive"))
    )
    (net (code "54") (name "Net-(U4-1)") (class "Default")
      (node (ref "R9") (pin "2") (pinfunction "2_2") (pintype "passive"))
      (node (ref "U4") (pin "G1") (pinfunction "1_G1") (pintype "passive"))
      (node (ref "U4") (pin "G2") (pinfunction "3_G2") (pintype "passive"))
      (node (ref "U4") (pin "S2") (pinfunction "2_S2") (pintype "passive"))
    )
    (net (code "55") (name "Net-(U5-5)") (class "Default")
      (node (ref "LED1") (pin "2") (pinfunction "2_2") (pintype "bidirectional"))
      (node (ref "U5") (pin "S1") (pinfunction "5_S1") (pintype "passive"))
    )
    (net (code "56") (name "Net-(U5-6)") (class "Default")
      (node (ref "LED2") (pin "2") (pinfunction "2_2") (pintype "bidirectional"))
      (node (ref "U5") (pin "D1") (pinfunction "6_D1") (pintype "passive"))
    )
    (net (code "57") (name "Net-(U6-CLKOUT)") (class "Default")
      (node (ref "CLKO") (pin "TP") (pinfunction "TP_TP") (pintype "input"))
      (node (ref "U6") (pin "1") (pinfunction "CLKOUT_1") (pintype "bidirectional"))
    )
    (net (code "58") (name "Net-(U6-EVI)") (class "Default")
      (node (ref "R13") (pin "1") (pinfunction "1_1") (pintype "passive"))
      (node (ref "U6") (pin "8") (pinfunction "EVI_8") (pintype "bidirectional"))
    )
    (net (code "59") (name "Net-(U6-VBACKUP)") (class "Default")
      (node (ref "C21") (pin "1") (pinfunction "1_1") (pintype "passive"))
      (node (ref "C23") (pin "1") (pinfunction "1_1") (pintype "passive"))
      (node (ref "R20") (pin "1") (pinfunction "1_1") (pintype "passive"))
      (node (ref "U6") (pin "6") (pinfunction "VBACKUP_6") (pintype "bidirectional"))
    )
    (net (code "60") (name "Net-(U6-~{INT})") (class "Default")
      (node (ref "INT") (pin "TP") (pinfunction "TP_TP") (pintype "input"))
      (node (ref "U6") (pin "2") (pinfunction "~{INT}_2") (pintype "bidirectional"))
    )
    (net (code "61") (name "SPI0_CE0") (class "Default")
      (node (ref "CTRL1") (pin "5") (pinfunction "CSN_5") (pintype "passive"))
      (node (ref "K1") (pin "24") (pinfunction "24_24") (pintype "passive"))
    )
    (net (code "62") (name "SPI0_CE1") (class "Default")
      (node (ref "CTRL2") (pin "5") (pinfunction "CSN_5") (pintype "passive"))
      (node (ref "K1") (pin "26") (pinfunction "26_26") (pintype "passive"))
    )
    (net (code "63") (name "SPI0_MISO") (class "Default")
      (node (ref "CTRL1") (pin "4") (pinfunction "SDO_4") (pintype "passive"))
      (node (ref "CTRL2") (pin "4") (pinfunction "SDO_4") (pintype "passive"))
      (node (ref "K1") (pin "21") (pinfunction "21_21") (pintype "passive"))
    )
    (net (code "64") (name "SPI0_MOSI") (class "Default")
      (node (ref "CTRL1") (pin "7") (pinfunction "SDI_7") (pintype "passive"))
      (node (ref "CTRL2") (pin "7") (pinfunction "SDI_7") (pintype "passive"))
      (node (ref "K1") (pin "19") (pinfunction "19_19") (pintype "passive"))
    )
    (net (code "65") (name "SPI0_SCLK") (class "Default")
      (node (ref "CTRL1") (pin "6") (pinfunction "SCK_6") (pintype "passive"))
      (node (ref "CTRL2") (pin "6") (pinfunction "SCK_6") (pintype "passive"))
      (node (ref "K1") (pin "23") (pinfunction "23_23") (pintype "passive"))
    )
    (net (code "66") (name "SW") (class "Default")
      (node (ref "L1") (pin "1") (pinfunction "1_1") (pintype "passive"))
      (node (ref "R8") (pin "1") (pinfunction "1_1") (pintype "passive"))
      (node (ref "U3") (pin "8") (pinfunction "SW_8") (pintype "output"))
    )
    (net (code "67") (name "UART_RX") (class "Default")
      (node (ref "K1") (pin "10") (pinfunction "10_10") (pintype "passive"))
    )
    (net (code "68") (name "UART_TX") (class "Default")
      (node (ref "K1") (pin "8") (pinfunction "8_8") (pintype "passive"))
    )
    (net (code "69") (name "unconnected-(CTRL1-DIR-Pad1)") (class "Default")
      (node (ref "CTRL1") (pin "1") (pinfunction "DIR_1") (pintype "passive"))
    )
    (net (code "70") (name "unconnected-(CTRL1-STEP-Pad2)") (class "Default")
      (node (ref "CTRL1") (pin "2") (pinfunction "STEP_2") (pintype "passive"))
    )
    (net (code "71") (name "unconnected-(CTRL2-DIR-Pad1)") (class "Default")
      (node (ref "CTRL2") (pin "1") (pinfunction "DIR_1") (pintype "passive"))
    )
    (net (code "72") (name "unconnected-(CTRL2-STEP-Pad2)") (class "Default")
      (node (ref "CTRL2") (pin "2") (pinfunction "STEP_2") (pintype "passive"))
    )
    (net (code "73") (name "unconnected-(FAN-PadRPM)") (class "Default")
      (node (ref "FAN") (pin "RPM") (pinfunction "RPM_RPM") (pintype "passive"))
    )
    (net (code "74") (name "unconnected-(K1-Pad1)") (class "Default")
      (node (ref "K1") (pin "1") (pinfunction "1_1") (pintype "passive"))
    )
    (net (code "75") (name "unconnected-(U2-NC-PadB1)") (class "Default")
      (node (ref "U2") (pin "B1") (pinfunction "NC_B1") (pintype "passive"))
    )
  )
)
